# DifferentialToSingle.net
KiCad netlist of a schematic drawn in Altium Designer
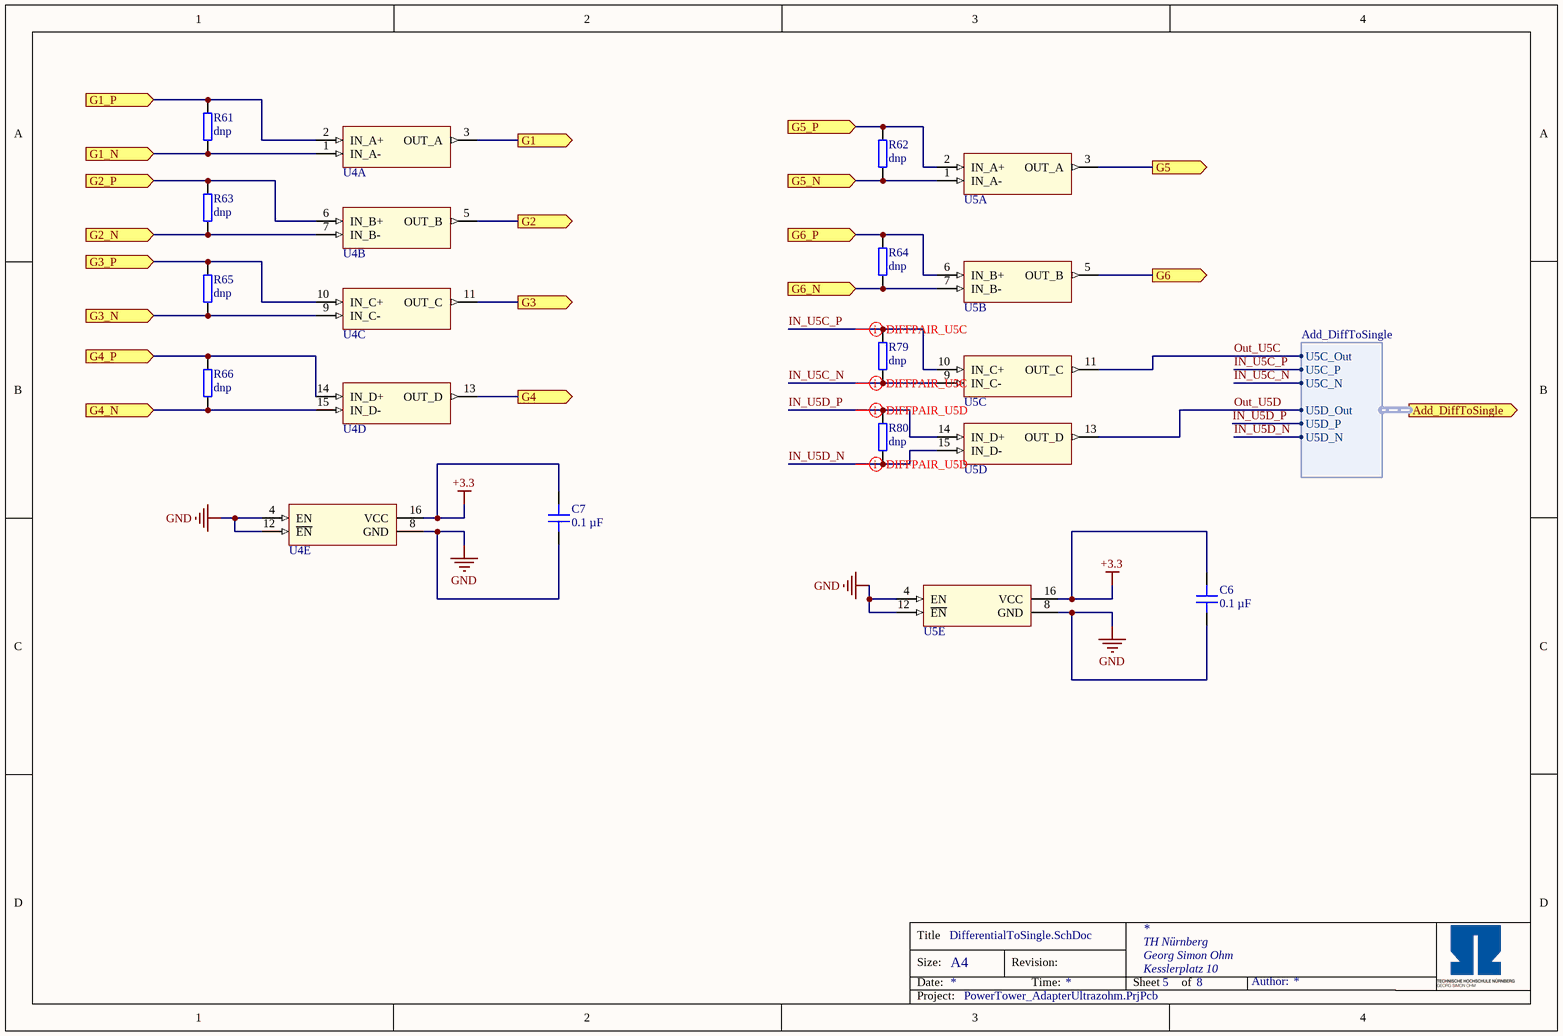
[diagram p0: DifferentialToSingle.SchDoc]

(export (version "E")
  (design (tool "Eeschema 10.0.6"))
  (components
    (comp (ref "C6")
      (value "0.1 µF")
      (footprint "C_0603")
      (description "Capacitor 0603, 50 VDC, 0.1 µF, X7R")
      (fields
        (field (name "MANUFACTURER PART NUMBER") "C0603X104K5RAC7411")
        (field (name "MANUFACTURER") "KEMET")
        (field (name "CREATED FROM") "MGremer")
      )
      (libsource (lib "user") (part "Capacitor"))
    )
    (comp (ref "C7")
      (value "0.1 µF")
      (footprint "C_0603")
      (description "Capacitor 0603, 50 VDC, 0.1 µF, X7R")
      (fields
        (field (name "MANUFACTURER PART NUMBER") "C0603X104K5RAC7411")
        (field (name "MANUFACTURER") "KEMET")
        (field (name "CREATED FROM") "MGremer")
      )
      (libsource (lib "user") (part "Capacitor"))
    )
    (comp (ref "R61")
      (value "dnp")
      (footprint "RES 0603_1608")
      (description "SMD resistor E24 series")
      (fields (field (name "CREATED FROM") "MGremer"))
      (libsource (lib "user") (part "Resistor"))
    )
    (comp (ref "R62")
      (value "dnp")
      (footprint "RES 0603_1608")
      (description "SMD resistor E24 series")
      (fields (field (name "CREATED FROM") "MGremer"))
      (libsource (lib "user") (part "Resistor"))
    )
    (comp (ref "R63")
      (value "dnp")
      (footprint "RES 0603_1608")
      (description "SMD resistor E24 series")
      (fields (field (name "CREATED FROM") "MGremer"))
      (libsource (lib "user") (part "Resistor"))
    )
    (comp (ref "R64")
      (value "dnp")
      (footprint "RES 0603_1608")
      (description "SMD resistor E24 series")
      (fields (field (name "CREATED FROM") "MGremer"))
      (libsource (lib "user") (part "Resistor"))
    )
    (comp (ref "R65")
      (value "dnp")
      (footprint "RES 0603_1608")
      (description "SMD resistor E24 series")
      (fields (field (name "CREATED FROM") "MGremer"))
      (libsource (lib "user") (part "Resistor"))
    )
    (comp (ref "R66")
      (value "dnp")
      (footprint "RES 0603_1608")
      (description "SMD resistor E24 series")
      (fields (field (name "CREATED FROM") "MGremer"))
      (libsource (lib "user") (part "Resistor"))
    )
    (comp (ref "R79")
      (value "dnp")
      (footprint "RES 0603_1608")
      (description "SMD resistor E24 series")
      (fields (field (name "CREATED FROM") "MGremer"))
      (libsource (lib "user") (part "Resistor"))
    )
    (comp (ref "R80")
      (value "dnp")
      (footprint "RES 0603_1608")
      (description "SMD resistor E24 series")
      (fields (field (name "CREATED FROM") "MGremer"))
      (libsource (lib "user") (part "Resistor"))
    )
    (comp (ref "U4")
      (value "DS26LV32ATM/NOPB")
      (footprint "TI_D-R-PDSO-G16_N")
      (description "3V Enhanced CMOS Quad Differential Line Receiver, 16-pin Narrow SOIC, Pb-Free")
      (fields
        (field (name "MANUFACTURER") "Texas Instruments")
        (field (name "LCSC PART NUMBER") "C59861")
        (field (name "CREATED FROM") "T. Wendt")
      )
      (libsource (lib "user") (part "DS26LV32ATM"))
    )
    (comp (ref "U5")
      (value "DS26LV32ATM/NOPB")
      (footprint "TI_D-R-PDSO-G16_N")
      (description "3V Enhanced CMOS Quad Differential Line Receiver, 16-pin Narrow SOIC, Pb-Free")
      (fields
        (field (name "MANUFACTURER") "Texas Instruments")
        (field (name "LCSC PART NUMBER") "C59861")
        (field (name "CREATED FROM") "T. Wendt")
      )
      (libsource (lib "user") (part "DS26LV32ATM"))
    )
  )
  (nets
    (net (code "2") (name "+3.3") (class "Default")
      (node (ref "C6") (pin "2") (pinfunction "2_2") (pintype "passive"))
      (node (ref "C7") (pin "2") (pinfunction "2_2") (pintype "passive"))
      (node (ref "U4") (pin "16") (pinfunction "VCC_16") (pintype "power_in"))
      (node (ref "U5") (pin "16") (pinfunction "VCC_16") (pintype "power_in"))
    )
    (net (code "3") (name "/G1") (class "Default")
      (node (ref "U4") (pin "3") (pinfunction "OUT_A_3") (pintype "output"))
    )
    (net (code "4") (name "/G1_N") (class "Default")
      (node (ref "R61") (pin "1") (pinfunction "1_1") (pintype "passive"))
      (node (ref "U4") (pin "1") (pinfunction "IN_A-_1") (pintype "input"))
    )
    (net (code "5") (name "/G1_P") (class "Default")
      (node (ref "R61") (pin "2") (pinfunction "2_2") (pintype "passive"))
      (node (ref "U4") (pin "2") (pinfunction "IN_A+_2") (pintype "input"))
    )
    (net (code "6") (name "/G2") (class "Default")
      (node (ref "U4") (pin "5") (pinfunction "OUT_B_5") (pintype "output"))
    )
    (net (code "7") (name "/G2_N") (class "Default")
      (node (ref "R63") (pin "1") (pinfunction "1_1") (pintype "passive"))
      (node (ref "U4") (pin "7") (pinfunction "IN_B-_7") (pintype "input"))
    )
    (net (code "8") (name "/G2_P") (class "Default")
      (node (ref "R63") (pin "2") (pinfunction "2_2") (pintype "passive"))
      (node (ref "U4") (pin "6") (pinfunction "IN_B+_6") (pintype "input"))
    )
    (net (code "9") (name "/G3") (class "Default")
      (node (ref "U4") (pin "11") (pinfunction "OUT_C_11") (pintype "output"))
    )
    (net (code "10") (name "/G3_N") (class "Default")
      (node (ref "R65") (pin "1") (pinfunction "1_1") (pintype "passive"))
      (node (ref "U4") (pin "9") (pinfunction "IN_C-_9") (pintype "input"))
    )
    (net (code "11") (name "/G3_P") (class "Default")
      (node (ref "R65") (pin "2") (pinfunction "2_2") (pintype "passive"))
      (node (ref "U4") (pin "10") (pinfunction "IN_C+_10") (pintype "input"))
    )
    (net (code "12") (name "/G4") (class "Default")
      (node (ref "U4") (pin "13") (pinfunction "OUT_D_13") (pintype "output"))
    )
    (net (code "13") (name "/G4_N") (class "Default")
      (node (ref "R66") (pin "1") (pinfunction "1_1") (pintype "passive"))
      (node (ref "U4") (pin "15") (pinfunction "IN_D-_15") (pintype "input"))
    )
    (net (code "14") (name "/G4_P") (class "Default")
      (node (ref "R66") (pin "2") (pinfunction "2_2") (pintype "passive"))
      (node (ref "U4") (pin "14") (pinfunction "IN_D+_14") (pintype "input"))
    )
    (net (code "15") (name "/G5") (class "Default")
      (node (ref "U5") (pin "3") (pinfunction "OUT_A_3") (pintype "output"))
    )
    (net (code "16") (name "/G5_N") (class "Default")
      (node (ref "R62") (pin "1") (pinfunction "1_1") (pintype "passive"))
      (node (ref "U5") (pin "1") (pinfunction "IN_A-_1") (pintype "input"))
    )
    (net (code "17") (name "/G5_P") (class "Default")
      (node (ref "R62") (pin "2") (pinfunction "2_2") (pintype "passive"))
      (node (ref "U5") (pin "2") (pinfunction "IN_A+_2") (pintype "input"))
    )
    (net (code "18") (name "/G6") (class "Default")
      (node (ref "U5") (pin "5") (pinfunction "OUT_B_5") (pintype "output"))
    )
    (net (code "19") (name "/G6_N") (class "Default")
      (node (ref "R64") (pin "1") (pinfunction "1_1") (pintype "passive"))
      (node (ref "U5") (pin "7") (pinfunction "IN_B-_7") (pintype "input"))
    )
    (net (code "20") (name "/G6_P") (class "Default")
      (node (ref "R64") (pin "2") (pinfunction "2_2") (pintype "passive"))
      (node (ref "U5") (pin "6") (pinfunction "IN_B+_6") (pintype "input"))
    )
    (net (code "21") (name "/IN_U5C_N") (class "Default")
      (node (ref "R79") (pin "1") (pinfunction "1_1") (pintype "passive"))
      (node (ref "U5") (pin "9") (pinfunction "IN_C-_9") (pintype "input"))
    )
    (net (code "22") (name "/IN_U5C_P") (class "Default")
      (node (ref "R79") (pin "2") (pinfunction "2_2") (pintype "passive"))
      (node (ref "U5") (pin "10") (pinfunction "IN_C+_10") (pintype "input"))
    )
    (net (code "23") (name "/IN_U5D_N") (class "Default")
      (node (ref "R80") (pin "1") (pinfunction "1_1") (pintype "passive"))
      (node (ref "U5") (pin "15") (pinfunction "IN_D-_15") (pintype "input"))
    )
    (net (code "24") (name "/IN_U5D_P") (class "Default")
      (node (ref "R80") (pin "2") (pinfunction "2_2") (pintype "passive"))
      (node (ref "U5") (pin "14") (pinfunction "IN_D+_14") (pintype "input"))
    )
    (net (code "25") (name "/Out_U5C") (class "Default")
      (node (ref "U5") (pin "11") (pinfunction "OUT_C_11") (pintype "output"))
    )
    (net (code "26") (name "/Out_U5D") (class "Default")
      (node (ref "U5") (pin "13") (pinfunction "OUT_D_13") (pintype "output"))
    )
    (net (code "28") (name "GND") (class "Default")
      (node (ref "C6") (pin "1") (pinfunction "1_1") (pintype "passive"))
      (node (ref "C7") (pin "1") (pinfunction "1_1") (pintype "passive"))
      (node (ref "U4") (pin "12") (pinfunction "~{EN}_12") (pintype "input"))
      (node (ref "U4") (pin "4") (pinfunction "EN_4") (pintype "input"))
      (node (ref "U4") (pin "8") (pinfunction "GND_8") (pintype "power_in"))
      (node (ref "U5") (pin "12") (pinfunction "~{EN}_12") (pintype "input"))
      (node (ref "U5") (pin "4") (pinfunction "EN_4") (pintype "input"))
      (node (ref "U5") (pin "8") (pinfunction "GND_8") (pintype "power_in"))
    )
  )
)
